# DSO_Control.net
KiCad netlist of a schematic drawn in Altium Designer
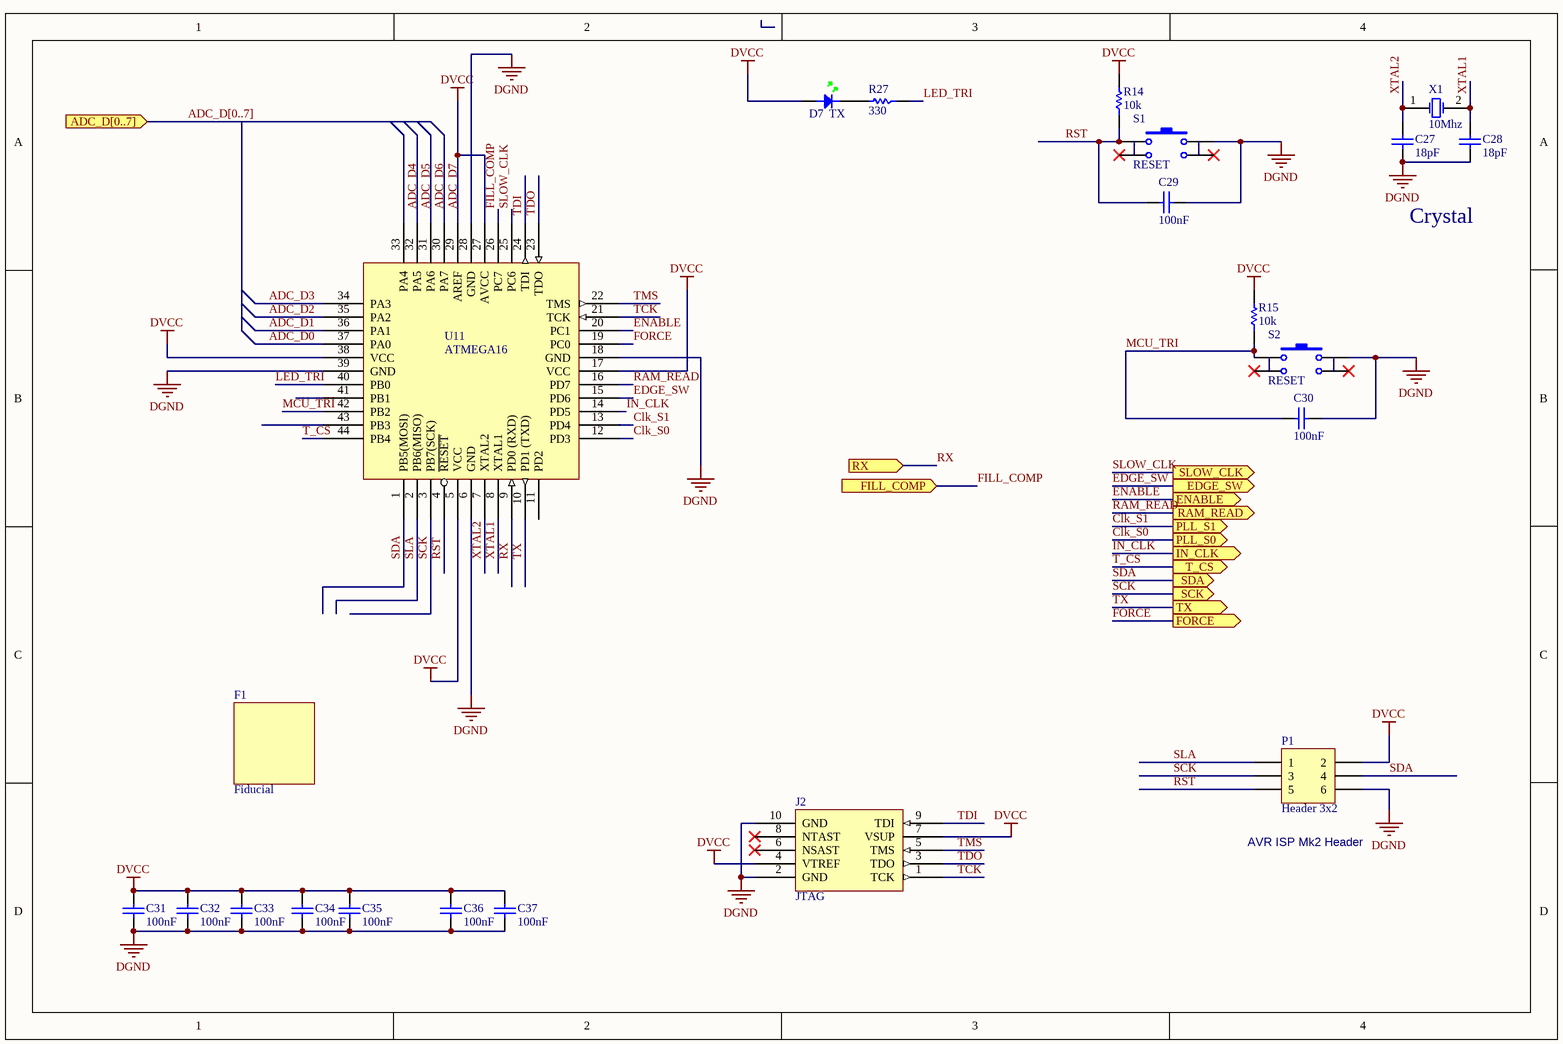
[diagram p0: DSO_Control.SchDoc]

(export (version "E")
  (design (tool "Eeschema 10.0.6"))
  (components
    (comp (ref "C27")
      (value "18pF")
      (footprint "0805C")
      (description "Capacitor")
      (fields (field (name "REVIEWED BY") "RM - 2018/08/05"))
      (libsource (lib "DSO") (part "C"))
    )
    (comp (ref "C28")
      (value "18pF")
      (footprint "0805C")
      (description "Capacitor")
      (fields (field (name "REVIEWED BY") "RM - 2018/08/05"))
      (libsource (lib "DSO") (part "C"))
    )
    (comp (ref "C29")
      (value "100nF")
      (footprint "0805C")
      (description "Capacitor")
      (fields (field (name "REVIEWED BY") "RM - 2018/08/05"))
      (libsource (lib "DSO") (part "C"))
    )
    (comp (ref "C30")
      (value "100nF")
      (footprint "0805C")
      (description "Capacitor")
      (fields (field (name "REVIEWED BY") "RM - 2018/08/05"))
      (libsource (lib "DSO") (part "C"))
    )
    (comp (ref "C31")
      (value "100nF")
      (footprint "0805C")
      (description "Capacitor")
      (fields (field (name "REVIEWED BY") "RM - 2018/08/05"))
      (libsource (lib "DSO") (part "C"))
    )
    (comp (ref "C32")
      (value "100nF")
      (footprint "0805C")
      (description "Capacitor")
      (fields (field (name "REVIEWED BY") "RM - 2018/08/05"))
      (libsource (lib "DSO") (part "C"))
    )
    (comp (ref "C33")
      (value "100nF")
      (footprint "0805C")
      (description "Capacitor")
      (fields (field (name "REVIEWED BY") "RM - 2018/08/05"))
      (libsource (lib "DSO") (part "C"))
    )
    (comp (ref "C34")
      (value "100nF")
      (footprint "0805C")
      (description "Capacitor")
      (fields (field (name "REVIEWED BY") "RM - 2018/08/05"))
      (libsource (lib "DSO") (part "C"))
    )
    (comp (ref "C35")
      (value "100nF")
      (footprint "0805C")
      (description "Capacitor")
      (fields (field (name "REVIEWED BY") "RM - 2018/08/05"))
      (libsource (lib "DSO") (part "C"))
    )
    (comp (ref "C36")
      (value "100nF")
      (footprint "0805C")
      (description "Capacitor")
      (fields (field (name "REVIEWED BY") "RM - 2018/08/05"))
      (libsource (lib "DSO") (part "C"))
    )
    (comp (ref "C37")
      (value "100nF")
      (footprint "0805C")
      (description "Capacitor")
      (fields (field (name "REVIEWED BY") "RM - 2018/08/05"))
      (libsource (lib "DSO") (part "C"))
    )
    (comp (ref "D7")
      (value "TX")
      (footprint "0805D-GREEN")
      (description "Light Emitting Diode")
      (fields (field (name "REVIEWED BY") "RM - 2018/08/05"))
      (libsource (lib "DSO") (part "LED GREEN"))
    )
    (comp (ref "F1") (value "Fiducial") (footprint "Fiducial") (libsource (lib "DSO") (part "Fiducial")))
    (comp (ref "J2")
      (value "JTAG")
      (footprint "BOXEDVERT10")
      (description "JTAG_CON")
      (fields (field (name "REVIEWED BY") "RM - 2018/08/05"))
      (libsource (lib "DSO") (part "JTAG_CON"))
    )
    (comp (ref "P1")
      (value "Header 3x2")
      (footprint "HDR3x2")
      (description "Header, 5-Pin")
      (fields (field (name "REVIEWED BY") "RM - 2018/08/05"))
      (libsource (lib "DSO") (part "Header 3x2"))
    )
    (comp (ref "R14")
      (value "10k")
      (footprint "0805")
      (description "Resistor")
      (fields (field (name "REVIEWED BY") "RM - 2018/08/05"))
      (libsource (lib "DSO") (part "R"))
    )
    (comp (ref "R15")
      (value "10k")
      (footprint "0805")
      (description "Resistor")
      (fields (field (name "REVIEWED BY") "RM - 2018/08/05"))
      (libsource (lib "DSO") (part "R"))
    )
    (comp (ref "R27")
      (value "330")
      (footprint "0805")
      (description "Resistor")
      (fields (field (name "REVIEWED BY") "RM - 2018/08/05"))
      (libsource (lib "DSO") (part "R"))
    )
    (comp (ref "S1")
      (value "RESET")
      (footprint "SPST PB SWITCH SMD")
      (description "Momentary Push Button Switch 1P 1T 2pins")
      (fields (field (name "REVIEWED BY") "RM - 2018/08/05"))
      (libsource (lib "DSO") (part "SW_PB_1P1T4"))
    )
    (comp (ref "S2")
      (value "RESET")
      (footprint "SPST PB SWITCH SMD")
      (description "Momentary Push Button Switch 1P 1T 2pins")
      (fields (field (name "REVIEWED BY") "RM - 2018/08/05"))
      (libsource (lib "DSO") (part "SW_PB_1P1T4"))
    )
    (comp (ref "U11")
      (value "ATMEGA16")
      (footprint "QFP-48")
      (description "ATMEGA16 Microcontroller")
      (fields (field (name "REVIEWED BY") "RM - 2018/08/05"))
      (libsource (lib "DSO") (part "ATMEGA16"))
    )
    (comp (ref "X1")
      (value "10Mhz")
      (footprint "XTAL_FLAT_SMD")
      (description "Crystal Oscillator")
      (fields (field (name "REVIEWED BY") "RM - 2018/08/05"))
      (libsource (lib "DSO") (part "XTAL"))
    )
  )
  (nets
    (net (code "1") (name "/ADC_D0") (class "Default")
      (node (ref "U11") (pin "37") (pinfunction "PA0_37") (pintype "passive"))
    )
    (net (code "2") (name "/ADC_D1") (class "Default")
      (node (ref "U11") (pin "36") (pinfunction "PA1_36") (pintype "passive"))
    )
    (net (code "3") (name "/ADC_D2") (class "Default")
      (node (ref "U11") (pin "35") (pinfunction "PA2_35") (pintype "passive"))
    )
    (net (code "4") (name "/ADC_D3") (class "Default")
      (node (ref "U11") (pin "34") (pinfunction "PA3_34") (pintype "passive"))
    )
    (net (code "5") (name "/ADC_D4") (class "Default")
      (node (ref "U11") (pin "33") (pinfunction "PA4_33") (pintype "passive"))
    )
    (net (code "6") (name "/ADC_D5") (class "Default")
      (node (ref "U11") (pin "32") (pinfunction "PA5_32") (pintype "passive"))
    )
    (net (code "7") (name "/ADC_D6") (class "Default")
      (node (ref "U11") (pin "31") (pinfunction "PA6_31") (pintype "passive"))
    )
    (net (code "8") (name "/ADC_D7") (class "Default")
      (node (ref "U11") (pin "30") (pinfunction "PA7_30") (pintype "passive"))
    )
    (net (code "10") (name "/Clk_S0") (class "Default")
      (node (ref "U11") (pin "12") (pinfunction "PD3_12") (pintype "passive"))
    )
    (net (code "11") (name "/Clk_S1") (class "Default")
      (node (ref "U11") (pin "13") (pinfunction "PD4_13") (pintype "passive"))
    )
    (net (code "12") (name "/EDGE_SW") (class "Default")
      (node (ref "U11") (pin "15") (pinfunction "PD6_15") (pintype "passive"))
    )
    (net (code "13") (name "/ENABLE") (class "Default")
      (node (ref "U11") (pin "20") (pinfunction "PC1_20") (pintype "passive"))
    )
    (net (code "14") (name "/FILL_COMP") (class "Default")
      (node (ref "U11") (pin "26") (pinfunction "PC7_26") (pintype "passive"))
    )
    (net (code "15") (name "/FORCE") (class "Default")
      (node (ref "U11") (pin "19") (pinfunction "PC0_19") (pintype "passive"))
    )
    (net (code "16") (name "/IN_CLK") (class "Default")
      (node (ref "U11") (pin "14") (pinfunction "PD5_14") (pintype "passive"))
    )
    (net (code "17") (name "/LED_TRI") (class "Default")
      (node (ref "R27") (pin "1") (pintype "passive"))
      (node (ref "U11") (pin "40") (pinfunction "PB0_40") (pintype "passive"))
    )
    (net (code "18") (name "/MCU_TRI") (class "Default")
      (node (ref "C30") (pin "1") (pinfunction "1_1") (pintype "passive"))
      (node (ref "R15") (pin "1") (pintype "passive"))
      (node (ref "S2") (pin "1") (pinfunction "1_1") (pintype "passive"))
      (node (ref "U11") (pin "42") (pinfunction "PB2_42") (pintype "passive"))
    )
    (net (code "19") (name "/RAM_READ") (class "Default")
      (node (ref "U11") (pin "16") (pinfunction "PD7_16") (pintype "passive"))
    )
    (net (code "20") (name "/RST") (class "Default")
      (node (ref "C29") (pin "1") (pinfunction "1_1") (pintype "passive"))
      (node (ref "P1") (pin "5") (pinfunction "5_5") (pintype "passive"))
      (node (ref "R14") (pin "1") (pintype "passive"))
      (node (ref "S1") (pin "1") (pinfunction "1_1") (pintype "passive"))
      (node (ref "U11") (pin "4") (pinfunction "~{RESET}_4") (pintype "passive"))
    )
    (net (code "21") (name "/RX") (class "Default")
      (node (ref "U11") (pin "9") (pinfunction "PD0_(RXD)_9") (pintype "input"))
    )
    (net (code "22") (name "/SCK") (class "Default")
      (node (ref "P1") (pin "3") (pinfunction "3_3") (pintype "passive"))
      (node (ref "U11") (pin "3") (pinfunction "PB7(SCK)_3") (pintype "passive"))
    )
    (net (code "23") (name "/SDA") (class "Default")
      (node (ref "P1") (pin "4") (pinfunction "4_4") (pintype "passive"))
      (node (ref "U11") (pin "1") (pinfunction "PB5(MOSI)_1") (pintype "passive"))
    )
    (net (code "24") (name "/SLA") (class "Default")
      (node (ref "P1") (pin "1") (pinfunction "1_1") (pintype "passive"))
      (node (ref "U11") (pin "2") (pinfunction "PB6(MISO)_2") (pintype "passive"))
    )
    (net (code "25") (name "/SLOW_CLK") (class "Default")
      (node (ref "U11") (pin "25") (pinfunction "PC6_25") (pintype "passive"))
    )
    (net (code "26") (name "/TCK") (class "Default")
      (node (ref "J2") (pin "1") (pinfunction "TCK_1") (pintype "output"))
      (node (ref "U11") (pin "21") (pinfunction "TCK_21") (pintype "input"))
    )
    (net (code "27") (name "/TDI") (class "Default")
      (node (ref "J2") (pin "9") (pinfunction "TDI_9") (pintype "input"))
      (node (ref "U11") (pin "24") (pinfunction "TDI_24") (pintype "output"))
    )
    (net (code "28") (name "/TDO") (class "Default")
      (node (ref "J2") (pin "3") (pinfunction "TDO_3") (pintype "output"))
      (node (ref "U11") (pin "23") (pinfunction "TDO_23") (pintype "input"))
    )
    (net (code "29") (name "/TMS") (class "Default")
      (node (ref "J2") (pin "5") (pinfunction "TMS_5") (pintype "input"))
      (node (ref "U11") (pin "22") (pinfunction "TMS_22") (pintype "output"))
    )
    (net (code "30") (name "/TX") (class "Default")
      (node (ref "U11") (pin "10") (pinfunction "PD1_(TXD)_10") (pintype "output"))
    )
    (net (code "31") (name "/T_CS") (class "Default")
      (node (ref "U11") (pin "44") (pinfunction "PB4_44") (pintype "passive"))
    )
    (net (code "32") (name "/XTAL1") (class "Default")
      (node (ref "C28") (pin "1") (pinfunction "1_1") (pintype "passive"))
      (node (ref "U11") (pin "8") (pinfunction "XTAL1_8") (pintype "passive"))
      (node (ref "X1") (pin "2") (pinfunction "OSC2_2") (pintype "passive"))
    )
    (net (code "33") (name "/XTAL2") (class "Default")
      (node (ref "C27") (pin "1") (pinfunction "1_1") (pintype "passive"))
      (node (ref "U11") (pin "7") (pinfunction "XTAL2_7") (pintype "passive"))
      (node (ref "X1") (pin "1") (pinfunction "OSC1_1") (pintype "passive"))
    )
    (net (code "34") (name "DGND") (class "Default")
      (node (ref "C27") (pin "2") (pinfunction "2_2") (pintype "passive"))
      (node (ref "C28") (pin "2") (pinfunction "2_2") (pintype "passive"))
      (node (ref "C29") (pin "2") (pinfunction "2_2") (pintype "passive"))
      (node (ref "C30") (pin "2") (pinfunction "2_2") (pintype "passive"))
      (node (ref "C31") (pin "2") (pinfunction "2_2") (pintype "passive"))
      (node (ref "C32") (pin "2") (pinfunction "2_2") (pintype "passive"))
      (node (ref "C33") (pin "2") (pinfunction "2_2") (pintype "passive"))
      (node (ref "C34") (pin "2") (pinfunction "2_2") (pintype "passive"))
      (node (ref "C35") (pin "2") (pinfunction "2_2") (pintype "passive"))
      (node (ref "C36") (pin "2") (pinfunction "2_2") (pintype "passive"))
      (node (ref "C37") (pin "2") (pinfunction "2_2") (pintype "passive"))
      (node (ref "J2") (pin "10") (pinfunction "GND_10") (pintype "passive"))
      (node (ref "J2") (pin "2") (pinfunction "GND_2") (pintype "passive"))
      (node (ref "P1") (pin "6") (pinfunction "6_6") (pintype "passive"))
      (node (ref "S1") (pin "2") (pinfunction "2_2") (pintype "passive"))
      (node (ref "S2") (pin "2") (pinfunction "2_2") (pintype "passive"))
      (node (ref "U11") (pin "18") (pinfunction "GND_18") (pintype "passive"))
      (node (ref "U11") (pin "28") (pinfunction "GND_28") (pintype "passive"))
      (node (ref "U11") (pin "39") (pinfunction "GND_39") (pintype "passive"))
      (node (ref "U11") (pin "6") (pinfunction "GND_6") (pintype "passive"))
    )
    (net (code "35") (name "DVCC") (class "Default")
      (node (ref "C31") (pin "1") (pinfunction "1_1") (pintype "passive"))
      (node (ref "C32") (pin "1") (pinfunction "1_1") (pintype "passive"))
      (node (ref "C33") (pin "1") (pinfunction "1_1") (pintype "passive"))
      (node (ref "C34") (pin "1") (pinfunction "1_1") (pintype "passive"))
      (node (ref "C35") (pin "1") (pinfunction "1_1") (pintype "passive"))
      (node (ref "C36") (pin "1") (pinfunction "1_1") (pintype "passive"))
      (node (ref "C37") (pin "1") (pinfunction "1_1") (pintype "passive"))
      (node (ref "D7") (pin "A") (pinfunction "A_A") (pintype "passive"))
      (node (ref "J2") (pin "4") (pinfunction "VTREF_4") (pintype "power_in"))
      (node (ref "J2") (pin "7") (pinfunction "VSUP_7") (pintype "passive"))
      (node (ref "P1") (pin "2") (pinfunction "2_2") (pintype "passive"))
      (node (ref "R14") (pin "2") (pintype "passive"))
      (node (ref "R15") (pin "2") (pintype "passive"))
      (node (ref "U11") (pin "17") (pinfunction "VCC_17") (pintype "passive"))
      (node (ref "U11") (pin "27") (pinfunction "AVCC_27") (pintype "passive"))
      (node (ref "U11") (pin "29") (pinfunction "AREF_29") (pintype "passive"))
      (node (ref "U11") (pin "38") (pinfunction "VCC_38") (pintype "passive"))
      (node (ref "U11") (pin "5") (pinfunction "VCC_5") (pintype "passive"))
    )
    (net (code "36") (name "Net-(D7-PadK)") (class "Default")
      (node (ref "D7") (pin "K") (pinfunction "K_K") (pintype "passive"))
      (node (ref "R27") (pin "2") (pintype "passive"))
    )
    (net (code "37") (name "unconnected-(J2-NSAST-Pad6)") (class "Default")
      (node (ref "J2") (pin "6") (pinfunction "NSAST_6") (pintype "passive+no_connect"))
    )
    (net (code "38") (name "unconnected-(J2-NTAST-Pad8)") (class "Default")
      (node (ref "J2") (pin "8") (pinfunction "NTAST_8") (pintype "passive+no_connect"))
    )
    (net (code "39") (name "unconnected-(S1-Pad3)") (class "Default")
      (node (ref "S1") (pin "3") (pinfunction "3_3") (pintype "passive+no_connect"))
    )
    (net (code "40") (name "unconnected-(S1-Pad4)") (class "Default")
      (node (ref "S1") (pin "4") (pinfunction "4_4") (pintype "passive+no_connect"))
    )
    (net (code "41") (name "unconnected-(S2-Pad3)") (class "Default")
      (node (ref "S2") (pin "3") (pinfunction "3_3") (pintype "passive+no_connect"))
    )
    (net (code "42") (name "unconnected-(S2-Pad4)") (class "Default")
      (node (ref "S2") (pin "4") (pinfunction "4_4") (pintype "passive+no_connect"))
    )
    (net (code "43") (name "unconnected-(U11-PB1-Pad41)") (class "Default")
      (node (ref "U11") (pin "41") (pinfunction "PB1_41") (pintype "passive"))
    )
    (net (code "44") (name "unconnected-(U11-PB3-Pad43)") (class "Default")
      (node (ref "U11") (pin "43") (pinfunction "PB3_43") (pintype "passive"))
    )
    (net (code "45") (name "unconnected-(U11-PD2-Pad11)") (class "Default")
      (node (ref "U11") (pin "11") (pinfunction "PD2_11") (pintype "passive"))
    )
  )
)
